# General-TX-Module.net
KiCad netlist of a schematic drawn in EAGLE
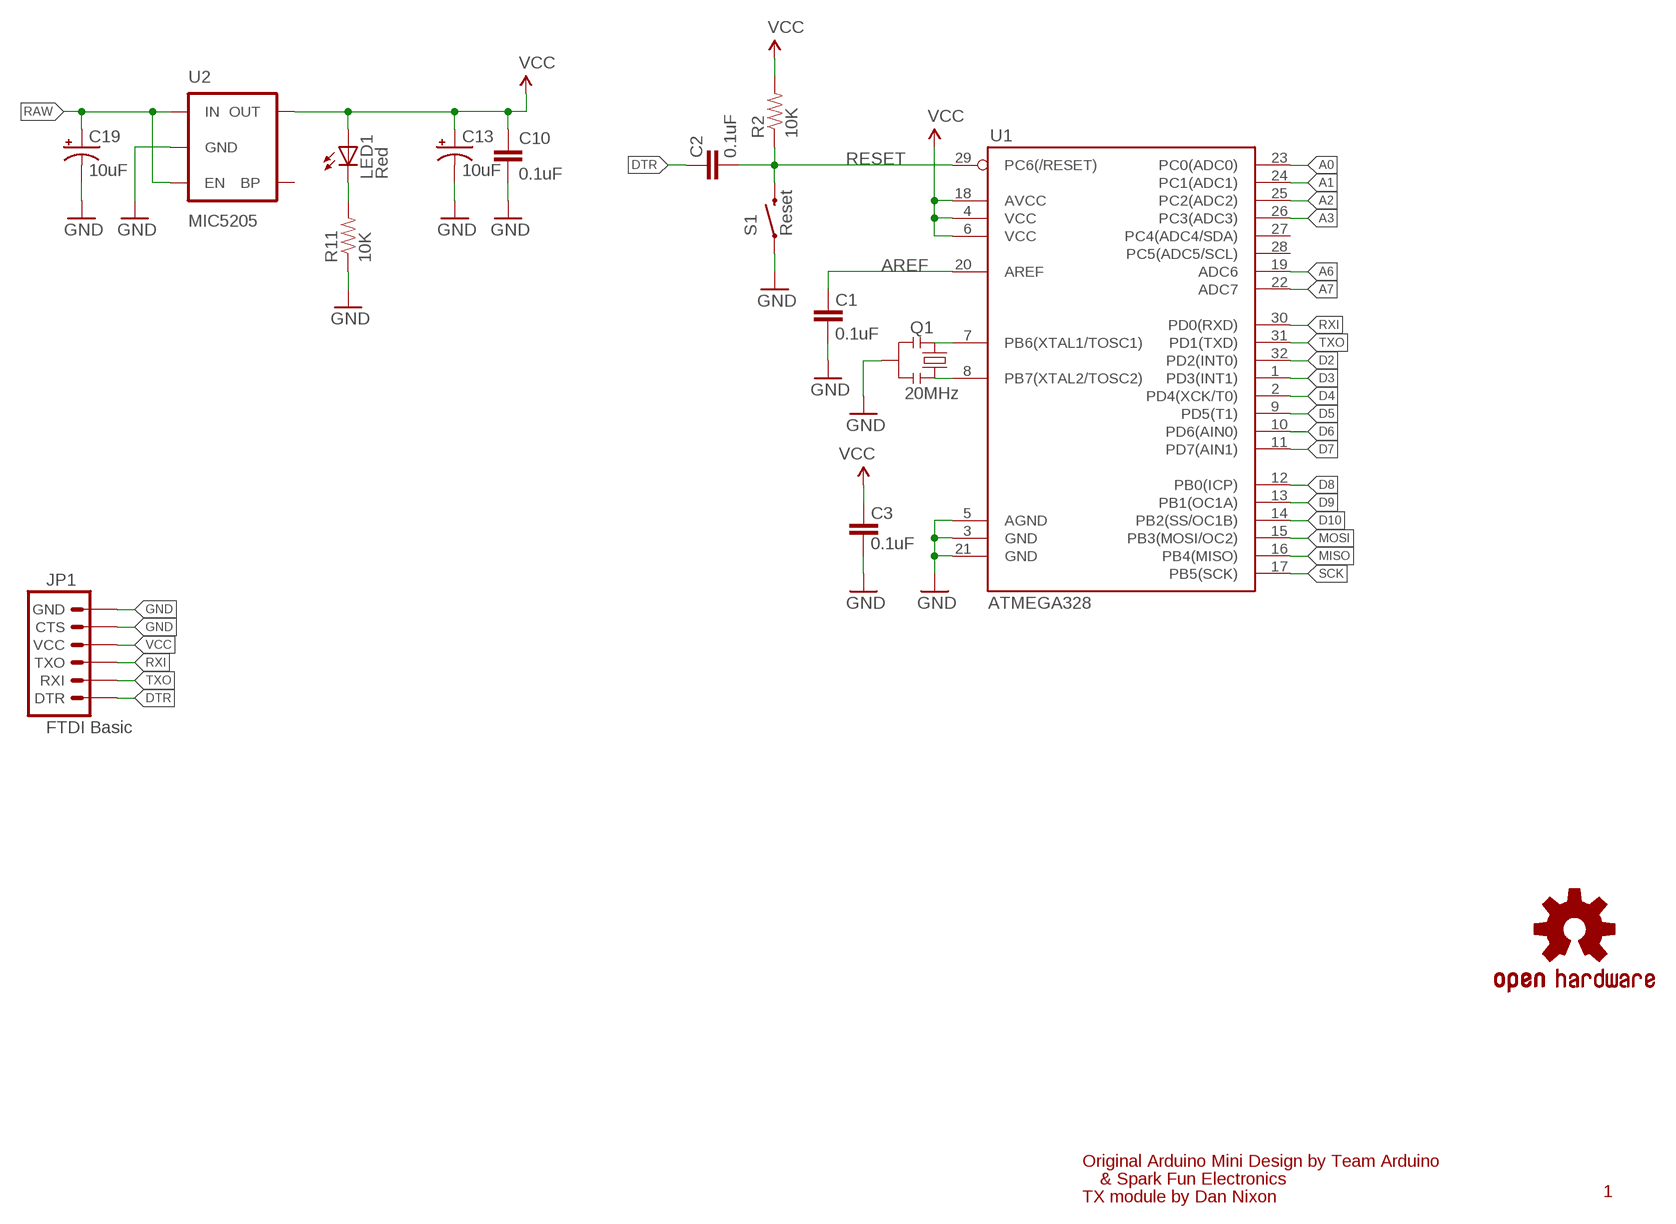
[diagram p0: schematic, sheet 1]

(export (version "E")
  (design (tool "Eeschema 10.0.6"))
  (components
    (comp (ref "C1")
      (value "0.1uF")
      (footprint "eagle-import:0603-CAP")
      (libsource (lib "eagle-import") (part "CAP0603-CAP"))
    )
    (comp (ref "C2")
      (value "0.1uF")
      (footprint "eagle-import:0603-CAP")
      (libsource (lib "eagle-import") (part "CAP0603-CAP"))
    )
    (comp (ref "C3")
      (value "0.1uF")
      (footprint "eagle-import:0603-CAP")
      (libsource (lib "eagle-import") (part "CAP0603-CAP"))
    )
    (comp (ref "C10")
      (value "0.1uF")
      (footprint "eagle-import:0603-CAP")
      (libsource (lib "eagle-import") (part "CAP0603-CAP"))
    )
    (comp (ref "C13")
      (value "10uF")
      (footprint "eagle-import:EIA3216")
      (libsource (lib "eagle-import") (part "CAP_POL1206"))
    )
    (comp (ref "C19")
      (value "10uF")
      (footprint "eagle-import:EIA3216")
      (libsource (lib "eagle-import") (part "CAP_POL1206"))
    )
    (comp (ref "JP1")
      (value "FTDI Basic")
      (footprint "eagle-import:1X06")
      (libsource (lib "eagle-import") (part "ARDUINO_SERIAL_PROGRAMPTH"))
    )
    (comp (ref "LED1")
      (value "Red")
      (footprint "eagle-import:0603-LED-ALT1")
      (libsource (lib "eagle-import") (part "LED"))
    )
    (comp (ref "Q1")
      (value "20MHz")
      (footprint "eagle-import:RESONATOR-SMD-1_1")
      (libsource (lib "eagle-import") (part "RESONATOR1{colon}1"))
    )
    (comp (ref "R2")
      (value "10K")
      (footprint "eagle-import:0603-RES")
      (libsource (lib "eagle-import") (part "RESISTOR0603-RES"))
    )
    (comp (ref "R11")
      (value "10K")
      (footprint "eagle-import:0603-RES")
      (libsource (lib "eagle-import") (part "RESISTOR0603-RES"))
    )
    (comp (ref "S1")
      (value "Reset")
      (footprint "eagle-import:TACTILE-SWITCH-SMD-ALT01")
      (libsource (lib "eagle-import") (part "SWITCH-MOMENTARY-2SMD-ALT01"))
    )
    (comp (ref "U$3")
      (value "OSHW-LOGOS")
      (footprint "eagle-import:OSHW-LOGO-S")
      (libsource (lib "eagle-import") (part "OSHW-LOGOS"))
    )
    (comp (ref "U1")
      (value "ATMEGA328")
      (footprint "eagle-import:TQFP32-08")
      (libsource (lib "eagle-import") (part "ATMEGA168"))
    )
    (comp (ref "U2")
      (value "MIC5205")
      (footprint "eagle-import:SOT23-5")
      (libsource (lib "eagle-import") (part "V_REG_LDOSMD"))
    )
  )
  (nets
    (net (code "1") (name "/AREF") (class "Default")
      (node (ref "C1") (pin "2") (pinfunction "2_2") (pintype "passive"))
      (node (ref "U1") (pin "20") (pinfunction "AREF_20") (pintype "bidirectional"))
    )
    (net (code "2") (name "/RESET") (class "Default")
      (node (ref "C2") (pin "1") (pinfunction "1_1") (pintype "passive"))
      (node (ref "R2") (pin "1") (pinfunction "1_1") (pintype "passive"))
      (node (ref "S1") (pin "3") (pinfunction "2_3") (pintype "passive"))
      (node (ref "S1") (pin "4") (pinfunction "2_4") (pintype "passive"))
      (node (ref "U1") (pin "29") (pinfunction "PC6(/RESET)_29") (pintype "bidirectional"))
    )
    (net (code "3") (name "A0") (class "Default")
      (node (ref "U1") (pin "23") (pinfunction "PC0(ADC0)_23") (pintype "bidirectional"))
    )
    (net (code "4") (name "A1") (class "Default")
      (node (ref "U1") (pin "24") (pinfunction "PC1(ADC1)_24") (pintype "bidirectional"))
    )
    (net (code "5") (name "A2") (class "Default")
      (node (ref "U1") (pin "25") (pinfunction "PC2(ADC2)_25") (pintype "bidirectional"))
    )
    (net (code "6") (name "A3") (class "Default")
      (node (ref "U1") (pin "26") (pinfunction "PC3(ADC3)_26") (pintype "bidirectional"))
    )
    (net (code "7") (name "A6") (class "Default")
      (node (ref "U1") (pin "19") (pinfunction "ADC6_19") (pintype "bidirectional"))
    )
    (net (code "8") (name "A7") (class "Default")
      (node (ref "U1") (pin "22") (pinfunction "ADC7_22") (pintype "bidirectional"))
    )
    (net (code "9") (name "D2") (class "Default")
      (node (ref "U1") (pin "32") (pinfunction "PD2(INT0)_32") (pintype "bidirectional"))
    )
    (net (code "10") (name "D3") (class "Default")
      (node (ref "U1") (pin "1") (pinfunction "PD3(INT1)_1") (pintype "bidirectional"))
    )
    (net (code "11") (name "D4") (class "Default")
      (node (ref "U1") (pin "2") (pinfunction "PD4(XCK/T0)_2") (pintype "bidirectional"))
    )
    (net (code "12") (name "D5") (class "Default")
      (node (ref "U1") (pin "9") (pinfunction "PD5(T1)_9") (pintype "bidirectional"))
    )
    (net (code "13") (name "D6") (class "Default")
      (node (ref "U1") (pin "10") (pinfunction "PD6(AIN0)_10") (pintype "bidirectional"))
    )
    (net (code "14") (name "D7") (class "Default")
      (node (ref "U1") (pin "11") (pinfunction "PD7(AIN1)_11") (pintype "bidirectional"))
    )
    (net (code "15") (name "D8") (class "Default")
      (node (ref "U1") (pin "12") (pinfunction "PB0(ICP)_12") (pintype "bidirectional"))
    )
    (net (code "16") (name "D9") (class "Default")
      (node (ref "U1") (pin "13") (pinfunction "PB1(OC1A)_13") (pintype "bidirectional"))
    )
    (net (code "17") (name "D10") (class "Default")
      (node (ref "U1") (pin "14") (pinfunction "PB2(SS/OC1B)_14") (pintype "bidirectional"))
    )
    (net (code "18") (name "DTR") (class "Default")
      (node (ref "C2") (pin "2") (pinfunction "2_2") (pintype "passive"))
      (node (ref "JP1") (pin "1") (pinfunction "DTR_1") (pintype "passive"))
    )
    (net (code "19") (name "GND") (class "Default")
      (node (ref "C1") (pin "1") (pinfunction "1_1") (pintype "passive"))
      (node (ref "C10") (pin "2") (pinfunction "2_2") (pintype "passive"))
      (node (ref "C13") (pin "C") (pinfunction "-_C") (pintype "passive"))
      (node (ref "C19") (pin "C") (pinfunction "-_C") (pintype "passive"))
      (node (ref "C3") (pin "1") (pinfunction "1_1") (pintype "passive"))
      (node (ref "JP1") (pin "5") (pinfunction "CTS_5") (pintype "passive"))
      (node (ref "JP1") (pin "6") (pinfunction "GND_6") (pintype "passive"))
      (node (ref "Q1") (pin "2") (pinfunction "2_2") (pintype "passive"))
      (node (ref "R11") (pin "1") (pinfunction "1_1") (pintype "passive"))
      (node (ref "S1") (pin "1") (pinfunction "1_1") (pintype "passive"))
      (node (ref "S1") (pin "2") (pinfunction "1_2") (pintype "passive"))
      (node (ref "U1") (pin "21") (pinfunction "GND_21") (pintype "bidirectional"))
      (node (ref "U1") (pin "3") (pinfunction "GND_3") (pintype "bidirectional"))
      (node (ref "U1") (pin "5") (pinfunction "AGND_5") (pintype "bidirectional"))
      (node (ref "U2") (pin "2") (pinfunction "GND_2") (pintype "input"))
    )
    (net (code "20") (name "MISO") (class "Default")
      (node (ref "U1") (pin "16") (pinfunction "PB4(MISO)_16") (pintype "bidirectional"))
    )
    (net (code "21") (name "MOSI") (class "Default")
      (node (ref "U1") (pin "15") (pinfunction "PB3(MOSI/OC2)_15") (pintype "bidirectional"))
    )
    (net (code "22") (name "Net-(LED1-PadC)") (class "Default")
      (node (ref "LED1") (pin "C") (pinfunction "C_C") (pintype "passive"))
      (node (ref "R11") (pin "2") (pinfunction "2_2") (pintype "passive"))
    )
    (net (code "23") (name "Net-(U1-PB6(XTAL1{slash}TOSC1))") (class "Default")
      (node (ref "Q1") (pin "1") (pinfunction "1_1") (pintype "passive"))
      (node (ref "U1") (pin "7") (pinfunction "PB6(XTAL1/TOSC1)_7") (pintype "bidirectional"))
    )
    (net (code "24") (name "Net-(U1-PB7(XTAL2{slash}TOSC2))") (class "Default")
      (node (ref "Q1") (pin "3") (pinfunction "3_3") (pintype "passive"))
      (node (ref "U1") (pin "8") (pinfunction "PB7(XTAL2/TOSC2)_8") (pintype "bidirectional"))
    )
    (net (code "25") (name "RAW") (class "Default")
      (node (ref "C19") (pin "A") (pinfunction "+_A") (pintype "passive"))
      (node (ref "U2") (pin "1") (pinfunction "IN_1") (pintype "input"))
      (node (ref "U2") (pin "3") (pinfunction "EN_3") (pintype "input"))
    )
    (net (code "26") (name "RXI") (class "Default")
      (node (ref "JP1") (pin "3") (pinfunction "TXO_3") (pintype "passive"))
      (node (ref "U1") (pin "30") (pinfunction "PD0(RXD)_30") (pintype "bidirectional"))
    )
    (net (code "27") (name "SCK") (class "Default")
      (node (ref "U1") (pin "17") (pinfunction "PB5(SCK)_17") (pintype "bidirectional"))
    )
    (net (code "28") (name "TXO") (class "Default")
      (node (ref "JP1") (pin "2") (pinfunction "RXI_2") (pintype "passive"))
      (node (ref "U1") (pin "31") (pinfunction "PD1(TXD)_31") (pintype "bidirectional"))
    )
    (net (code "29") (name "VCC") (class "Default")
      (node (ref "C10") (pin "1") (pinfunction "1_1") (pintype "passive"))
      (node (ref "C13") (pin "A") (pinfunction "+_A") (pintype "passive"))
      (node (ref "C3") (pin "2") (pinfunction "2_2") (pintype "passive"))
      (node (ref "JP1") (pin "4") (pinfunction "VCC_4") (pintype "passive"))
      (node (ref "LED1") (pin "A") (pinfunction "A_A") (pintype "passive"))
      (node (ref "R2") (pin "2") (pinfunction "2_2") (pintype "passive"))
      (node (ref "U1") (pin "18") (pinfunction "AVCC_18") (pintype "bidirectional"))
      (node (ref "U1") (pin "4") (pinfunction "VCC_4") (pintype "bidirectional"))
      (node (ref "U1") (pin "6") (pinfunction "VCC_6") (pintype "bidirectional"))
      (node (ref "U2") (pin "5") (pinfunction "OUT_5") (pintype "passive"))
    )
    (net (code "30") (name "unconnected-(U1-PC4(ADC4{slash}SDA)-Pad27)") (class "Default")
      (node (ref "U1") (pin "27") (pinfunction "PC4(ADC4/SDA)_27") (pintype "bidirectional"))
    )
    (net (code "31") (name "unconnected-(U1-PC5(ADC5{slash}SCL)-Pad28)") (class "Default")
      (node (ref "U1") (pin "28") (pinfunction "PC5(ADC5/SCL)_28") (pintype "bidirectional"))
    )
    (net (code "32") (name "unconnected-(U2-BP-Pad4)") (class "Default")
      (node (ref "U2") (pin "4") (pinfunction "BP_4") (pintype "input"))
    )
  )
)
